# EE209_Schematic.net
KiCad netlist of a schematic drawn in Altium Designer
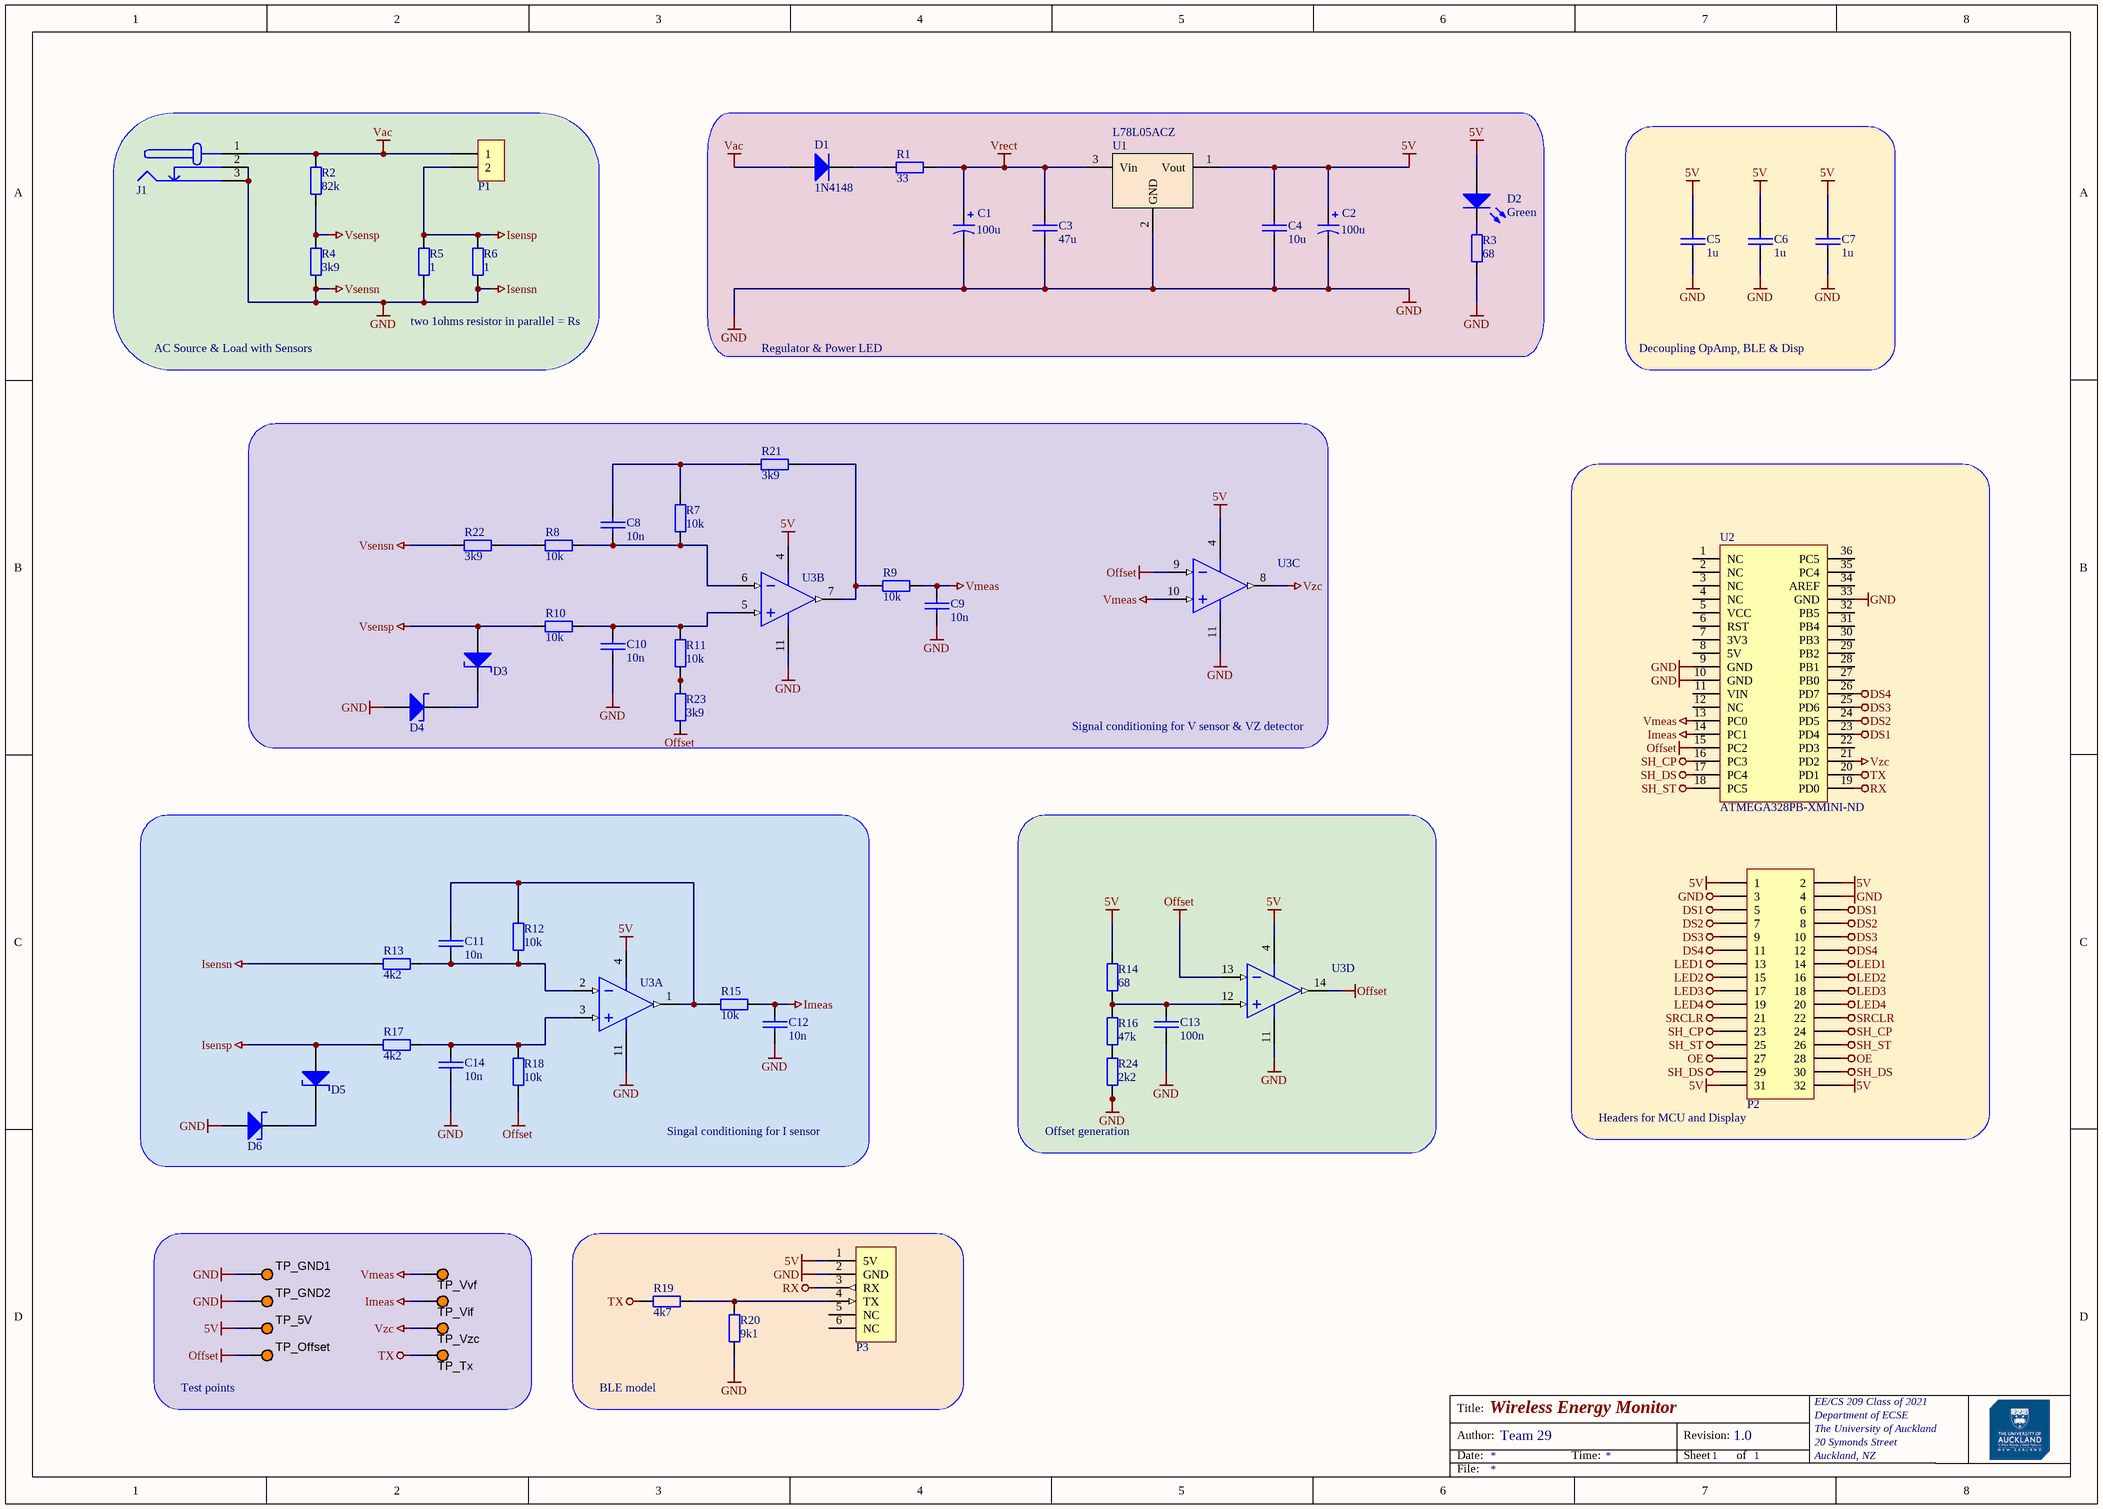
[diagram p0: EE209_Schematic.SchDoc]

(export (version "E")
  (design (tool "Eeschema 10.0.6"))
  (components
    (comp (ref "C1")
      (value "100u")
      (footprint "CAP-RAD-2.5mm Pitch")
      (description "Electrolytic capacitor with radial package, 2mm pitch and 5.2mm diameter")
      (fields (field (name "PUBLISHER") "Altium Limited"))
      (libsource (lib "EE209_Library") (part "ElecCap_TH_2P0"))
    )
    (comp (ref "C2")
      (value "100u")
      (footprint "CAP-RAD-2.5mm Pitch")
      (description "Electrolytic capacitor with radial package, 2mm pitch and 5.2mm diameter")
      (fields (field (name "PUBLISHER") "Altium Limited"))
      (libsource (lib "EE209_Library") (part "ElecCap_TH_2P0"))
    )
    (comp (ref "C3")
      (value "47u")
      (footprint "CCAP-5P0")
      (description "TH ceramic capacitor with 5mm pitch")
      (libsource (lib "EE209_Library") (part "CerCap_TH_5P0"))
    )
    (comp (ref "C4")
      (value "10u")
      (footprint "CCAP-5P0")
      (description "TH ceramic capacitor with 5mm pitch")
      (libsource (lib "EE209_Library") (part "CerCap_TH_5P0"))
    )
    (comp (ref "C5")
      (value "1u")
      (footprint "CCAP-5P0")
      (description "TH ceramic capacitor with 5mm pitch")
      (libsource (lib "EE209_Library") (part "CerCap_TH_5P0"))
    )
    (comp (ref "C6")
      (value "1u")
      (footprint "CCAP-5P0")
      (description "TH ceramic capacitor with 5mm pitch")
      (libsource (lib "EE209_Library") (part "CerCap_TH_5P0"))
    )
    (comp (ref "C7")
      (value "1u")
      (footprint "CCAP-5P0")
      (description "TH ceramic capacitor with 5mm pitch")
      (libsource (lib "EE209_Library") (part "CerCap_TH_5P0"))
    )
    (comp (ref "C8")
      (value "10n")
      (footprint "CCAP-5P0")
      (description "TH ceramic capacitor with 5mm pitch")
      (libsource (lib "EE209_Library") (part "CerCap_TH_5P0"))
    )
    (comp (ref "C9")
      (value "10n")
      (footprint "CCAP-5P0")
      (description "TH ceramic capacitor with 5mm pitch")
      (libsource (lib "EE209_Library") (part "CerCap_TH_5P0"))
    )
    (comp (ref "C10")
      (value "10n")
      (footprint "CCAP-5P0")
      (description "TH ceramic capacitor with 5mm pitch")
      (libsource (lib "EE209_Library") (part "CerCap_TH_5P0"))
    )
    (comp (ref "C11")
      (value "10n")
      (footprint "CCAP-5P0")
      (description "TH ceramic capacitor with 5mm pitch")
      (libsource (lib "EE209_Library") (part "CerCap_TH_5P0"))
    )
    (comp (ref "C12")
      (value "10n")
      (footprint "CCAP-5P0")
      (description "TH ceramic capacitor with 5mm pitch")
      (libsource (lib "EE209_Library") (part "CerCap_TH_5P0"))
    )
    (comp (ref "C13")
      (value "100n")
      (footprint "CCAP-5P0")
      (description "TH ceramic capacitor with 5mm pitch")
      (libsource (lib "EE209_Library") (part "CerCap_TH_5P0"))
    )
    (comp (ref "C14")
      (value "10n")
      (footprint "CCAP-5P0")
      (description "TH ceramic capacitor with 5mm pitch")
      (libsource (lib "EE209_Library") (part "CerCap_TH_5P0"))
    )
    (comp (ref "D1")
      (value "1N4148")
      (footprint "AXIAL-DIODE-0.4")
      (description "1N4148 100V 200mA axial diode")
      (fields
        (field (name "MANUFACTURER") "ON Semiconductor")
        (field (name "MANUFACTURER PART NUMBER") "1N4148TR")
      )
      (libsource (lib "EE209_Library") (part "1N4148_TH_4AX0"))
    )
    (comp (ref "D2")
      (value "Green")
      (footprint "LED")
      (description "Typical throughole GaAs LED with 2.54mm pitch")
      (fields (field (name "MANUFACTURER") "Generic Components") (field (name "PUBLISHER") "Altium Limited"))
      (libsource (lib "EE209_Library") (part "LED_TH_2P54"))
    )
    (comp (ref "D3")
      (value "BZX79-CXVX")
      (footprint "AXIAL-Zener-0.4")
      (description "Axial zener diode BZX79 series")
      (fields
        (field (name "MANUFACTURER") "Nexperia USA Inc.")
        (field (name "MANUFACTURER PART NUMBER") "BZX79-C4V7,143")
      )
      (libsource (lib "EE209_Library") (part "Zener_TH_4AX0"))
    )
    (comp (ref "D4")
      (value "BZX79-CXVX")
      (footprint "AXIAL-Zener-0.4")
      (description "Axial zener diode BZX79 series")
      (fields
        (field (name "MANUFACTURER") "Nexperia USA Inc.")
        (field (name "MANUFACTURER PART NUMBER") "BZX79-C4V7,143")
      )
      (libsource (lib "EE209_Library") (part "Zener_TH_4AX0"))
    )
    (comp (ref "D5")
      (value "BZX79-CXVX")
      (footprint "AXIAL-Zener-0.4")
      (description "Axial zener diode BZX79 series")
      (fields
        (field (name "MANUFACTURER") "Nexperia USA Inc.")
        (field (name "MANUFACTURER PART NUMBER") "BZX79-C4V7,143")
      )
      (libsource (lib "EE209_Library") (part "Zener_TH_4AX0"))
    )
    (comp (ref "D6")
      (value "BZX79-CXVX")
      (footprint "AXIAL-Zener-0.4")
      (description "Axial zener diode BZX79 series")
      (fields
        (field (name "MANUFACTURER") "Nexperia USA Inc.")
        (field (name "MANUFACTURER PART NUMBER") "BZX79-C4V7,143")
      )
      (libsource (lib "EE209_Library") (part "Zener_TH_4AX0"))
    )
    (comp (ref "J1")
      (value "DC barrel jack")
      (footprint "AC-Socket")
      (description "DC barrel jack connection to AC source")
      (libsource (lib "EE209_Library") (part "AC_Input"))
    )
    (comp (ref "P1")
      (value "Dual Banana Plugs")
      (footprint "Dual Banana Plug")
      (description "Dual banana plugs connection to the AC load")
      (fields (field (name "PUBLISHER") "Altium Limited"))
      (libsource (lib "EE209_Library") (part "AC_Output"))
    )
    (comp (ref "P2")
      (value "Display")
      (footprint "Display")
      (description "16-Pin Header Connecting Display")
      (libsource (lib "EE209_Library") (part "Display"))
    )
    (comp (ref "P3")
      (value "BLE Module Header")
      (footprint "HM10_HDR1X6")
      (description "2.54mm pitch 6-pin header for BLE module")
      (fields (field (name "PUBLISHER") "Altium Limited"))
      (libsource (lib "EE209_Library") (part "BLEModule_TH"))
    )
    (comp (ref "R1")
      (value "33")
      (footprint "AXIAL-0.4")
      (description "Through hole resistor")
      (fields (field (name "PUBLISHER") "Altium Limited"))
      (libsource (lib "") (part "Res_TH_0AX4_1"))
    )
    (comp (ref "R2")
      (value "82k")
      (footprint "AXIAL-0.4")
      (description "Through hole resistor")
      (fields (field (name "PUBLISHER") "Altium Limited"))
      (libsource (lib "EE209_Library") (part "Res_TH_0AX4"))
    )
    (comp (ref "R3")
      (value "68")
      (footprint "AXIAL-0.4")
      (description "Through hole resistor")
      (fields (field (name "PUBLISHER") "Altium Limited"))
      (libsource (lib "EE209_Library") (part "Res_TH_0AX4"))
    )
    (comp (ref "R4")
      (value "3k9")
      (footprint "AXIAL-0.4")
      (description "Through hole resistor")
      (fields (field (name "PUBLISHER") "Altium Limited"))
      (libsource (lib "EE209_Library") (part "Res_TH_0AX4"))
    )
    (comp (ref "R5")
      (value "1")
      (footprint "AXIAL-0.4")
      (description "Through hole resistor")
      (fields (field (name "PUBLISHER") "Altium Limited"))
      (libsource (lib "EE209_Library") (part "Res_TH_0AX4"))
    )
    (comp (ref "R6")
      (value "1")
      (footprint "AXIAL-0.4")
      (description "Through hole resistor")
      (fields (field (name "PUBLISHER") "Altium Limited"))
      (libsource (lib "EE209_Library") (part "Res_TH_0AX4"))
    )
    (comp (ref "R7")
      (value "10k")
      (footprint "AXIAL-0.4")
      (description "Through hole resistor")
      (fields (field (name "PUBLISHER") "Altium Limited"))
      (libsource (lib "EE209_Library") (part "Res_TH_0AX4"))
    )
    (comp (ref "R8")
      (value "10k")
      (footprint "AXIAL-0.4")
      (description "Through hole resistor")
      (fields (field (name "PUBLISHER") "Altium Limited"))
      (libsource (lib "") (part "Res_TH_0AX4_1"))
    )
    (comp (ref "R9")
      (value "10k")
      (footprint "AXIAL-0.4")
      (description "Through hole resistor")
      (fields (field (name "PUBLISHER") "Altium Limited"))
      (libsource (lib "") (part "Res_TH_0AX4_1"))
    )
    (comp (ref "R10")
      (value "10k")
      (footprint "AXIAL-0.4")
      (description "Through hole resistor")
      (fields (field (name "PUBLISHER") "Altium Limited"))
      (libsource (lib "") (part "Res_TH_0AX4_1"))
    )
    (comp (ref "R11")
      (value "10k")
      (footprint "AXIAL-0.4")
      (description "Through hole resistor")
      (fields (field (name "PUBLISHER") "Altium Limited"))
      (libsource (lib "EE209_Library") (part "Res_TH_0AX4"))
    )
    (comp (ref "R12")
      (value "10k")
      (footprint "AXIAL-0.4")
      (description "Through hole resistor")
      (fields (field (name "PUBLISHER") "Altium Limited"))
      (libsource (lib "EE209_Library") (part "Res_TH_0AX4"))
    )
    (comp (ref "R13")
      (value "4k2")
      (footprint "AXIAL-0.4")
      (description "Through hole resistor")
      (fields (field (name "PUBLISHER") "Altium Limited"))
      (libsource (lib "") (part "Res_TH_0AX4_1"))
    )
    (comp (ref "R14")
      (value "68")
      (footprint "AXIAL-0.4")
      (description "Through hole resistor")
      (fields (field (name "PUBLISHER") "Altium Limited"))
      (libsource (lib "EE209_Library") (part "Res_TH_0AX4"))
    )
    (comp (ref "R15")
      (value "10k")
      (footprint "AXIAL-0.4")
      (description "Through hole resistor")
      (fields (field (name "PUBLISHER") "Altium Limited"))
      (libsource (lib "") (part "Res_TH_0AX4_1"))
    )
    (comp (ref "R16")
      (value "47k")
      (footprint "AXIAL-0.4")
      (description "Through hole resistor")
      (fields (field (name "PUBLISHER") "Altium Limited"))
      (libsource (lib "EE209_Library") (part "Res_TH_0AX4"))
    )
    (comp (ref "R17")
      (value "4k2")
      (footprint "AXIAL-0.4")
      (description "Through hole resistor")
      (fields (field (name "PUBLISHER") "Altium Limited"))
      (libsource (lib "") (part "Res_TH_0AX4_1"))
    )
    (comp (ref "R18")
      (value "10k")
      (footprint "AXIAL-0.4")
      (description "Through hole resistor")
      (fields (field (name "PUBLISHER") "Altium Limited"))
      (libsource (lib "EE209_Library") (part "Res_TH_0AX4"))
    )
    (comp (ref "R19")
      (value "4k7")
      (footprint "AXIAL-0.4")
      (description "Through hole resistor")
      (fields (field (name "PUBLISHER") "Altium Limited"))
      (libsource (lib "") (part "Res_TH_0AX4_1"))
    )
    (comp (ref "R20")
      (value "9k1")
      (footprint "AXIAL-0.4")
      (description "Through hole resistor")
      (fields (field (name "PUBLISHER") "Altium Limited"))
      (libsource (lib "EE209_Library") (part "Res_TH_0AX4"))
    )
    (comp (ref "R21")
      (value "3k9")
      (footprint "AXIAL-0.4")
      (description "Through hole resistor")
      (fields (field (name "PUBLISHER") "Altium Limited"))
      (libsource (lib "") (part "Res_TH_0AX4_1"))
    )
    (comp (ref "R22")
      (value "3k9")
      (footprint "AXIAL-0.4")
      (description "Through hole resistor")
      (fields (field (name "PUBLISHER") "Altium Limited"))
      (libsource (lib "") (part "Res_TH_0AX4_1"))
    )
    (comp (ref "R23")
      (value "3k9")
      (footprint "AXIAL-0.4")
      (description "Through hole resistor")
      (fields (field (name "PUBLISHER") "Altium Limited"))
      (libsource (lib "EE209_Library") (part "Res_TH_0AX4"))
    )
    (comp (ref "R24")
      (value "2k2")
      (footprint "AXIAL-0.4")
      (description "Through hole resistor")
      (fields (field (name "PUBLISHER") "Altium Limited"))
      (libsource (lib "EE209_Library") (part "Res_TH_0AX4"))
    )
    (comp (ref "TP_5V")
      (value "5003")
      (footprint "TP_TH")
      (description "Test Point, Orange, 1-Pin THD, RoHS")
      (libsource (lib "EE209_Library") (part "TestPoint"))
    )
    (comp (ref "TP_GND1")
      (value "5003")
      (footprint "TP_TH")
      (description "Test Point, Orange, 1-Pin THD, RoHS")
      (libsource (lib "EE209_Library") (part "TestPoint"))
    )
    (comp (ref "TP_GND2")
      (value "5003")
      (footprint "TP_TH")
      (description "Test Point, Orange, 1-Pin THD, RoHS")
      (libsource (lib "EE209_Library") (part "TestPoint"))
    )
    (comp (ref "TP_Offset")
      (value "5003")
      (footprint "TP_TH")
      (description "Test Point, Orange, 1-Pin THD, RoHS")
      (libsource (lib "EE209_Library") (part "TestPoint"))
    )
    (comp (ref "TP_Tx")
      (value "5003")
      (footprint "TP_TH")
      (description "Test Point, Orange, 1-Pin THD, RoHS")
      (libsource (lib "EE209_Library") (part "TestPoint"))
    )
    (comp (ref "TP_Vif")
      (value "5003")
      (footprint "TP_TH")
      (description "Test Point, Orange, 1-Pin THD, RoHS")
      (libsource (lib "EE209_Library") (part "TestPoint"))
    )
    (comp (ref "TP_Vvf")
      (value "5003")
      (footprint "TP_TH")
      (description "Test Point, Orange, 1-Pin THD, RoHS")
      (libsource (lib "EE209_Library") (part "TestPoint"))
    )
    (comp (ref "TP_Vzc")
      (value "5003")
      (footprint "TP_TH")
      (description "Test Point, Orange, 1-Pin THD, RoHS")
      (libsource (lib "EE209_Library") (part "TestPoint"))
    )
    (comp (ref "U1")
      (value "L78L05ACZ")
      (footprint "TO-92")
      (description "Voltage Regulator 5V")
      (fields
        (field (name "MANUFACTURER") "ON Semiconductor")
        (field (name "MANUFACTURER PART NUMBER") "LM78L05ACZX")
      )
      (libsource (lib "EE209_Library") (part "L78L05_TH_TO92"))
    )
    (comp (ref "U2")
      (value "ATmega328PB Xplained Mini Header")
      (footprint "ATmeg328P Xplained")
      (description "Dual 18-pin headers connecting to ATmega328PB Xplained Mini")
      (fields
        (field (name "MANUFACTURER") "Microchip Technology")
        (field (name "MANUFACTURER PART NUMBER") "ATMEGA328PB-XMINI")
        (field (name "SUPPLIER PART NUMBER 1") "ATMEGA328PB-XMINI-ND")
      )
      (libsource (lib "EE209_Library") (part "ATmega328PBXplained_TH"))
    )
    (comp (ref "U3")
      (value "LM324")
      (footprint "DIP-14")
      (description "IC OPAMP GP 14DIP")
      (fields
        (field (name "MANUFACTURER") "ON Semiconductor")
        (field (name "MANUFACTURER PART NUMBER") "LM324N")
      )
      (libsource (lib "EE209_Library") (part "LM324N_TH_DIP16"))
    )
  )
  (nets
    (net (code "1") (name "5V") (class "Default")
      (node (ref "C2") (pin "1") (pinfunction "1_1") (pintype "passive"))
      (node (ref "C4") (pin "1") (pinfunction "1_1") (pintype "passive"))
      (node (ref "C5") (pin "1") (pinfunction "1_1") (pintype "passive"))
      (node (ref "C6") (pin "1") (pinfunction "1_1") (pintype "passive"))
      (node (ref "C7") (pin "1") (pinfunction "1_1") (pintype "passive"))
      (node (ref "D2") (pin "1") (pinfunction "A_1") (pintype "passive"))
      (node (ref "P2") (pin "1") (pinfunction "1_1") (pintype "passive"))
      (node (ref "P2") (pin "2") (pinfunction "2_2") (pintype "passive"))
      (node (ref "P2") (pin "31") (pinfunction "31_31") (pintype "passive"))
      (node (ref "P2") (pin "32") (pinfunction "32_32") (pintype "passive"))
      (node (ref "P3") (pin "1") (pinfunction "5V_1") (pintype "passive"))
      (node (ref "R14") (pin "2") (pinfunction "2_2") (pintype "passive"))
      (node (ref "TP_5V") (pin "1") (pinfunction "1_1") (pintype "passive"))
      (node (ref "U1") (pin "1") (pinfunction "Vout_1") (pintype "passive"))
      (node (ref "U3") (pin "4") (pinfunction "VDD_4") (pintype "power_in"))
    )
    (net (code "2") (name "DS1") (class "Default")
      (node (ref "P2") (pin "5") (pinfunction "5_5") (pintype "passive"))
      (node (ref "P2") (pin "6") (pinfunction "6_6") (pintype "passive"))
      (node (ref "U2") (pin "23") (pinfunction "PD4_23") (pintype "passive"))
    )
    (net (code "3") (name "DS2") (class "Default")
      (node (ref "P2") (pin "7") (pinfunction "7_7") (pintype "passive"))
      (node (ref "P2") (pin "8") (pinfunction "8_8") (pintype "passive"))
      (node (ref "U2") (pin "24") (pinfunction "PD5_24") (pintype "passive"))
    )
    (net (code "4") (name "DS3") (class "Default")
      (node (ref "P2") (pin "10") (pinfunction "10_10") (pintype "passive"))
      (node (ref "P2") (pin "9") (pinfunction "9_9") (pintype "passive"))
      (node (ref "U2") (pin "25") (pinfunction "PD6_25") (pintype "passive"))
    )
    (net (code "5") (name "DS4") (class "Default")
      (node (ref "P2") (pin "11") (pinfunction "11_11") (pintype "passive"))
      (node (ref "P2") (pin "12") (pinfunction "12_12") (pintype "passive"))
      (node (ref "U2") (pin "26") (pinfunction "PD7_26") (pintype "passive"))
    )
    (net (code "6") (name "GND") (class "Default")
      (node (ref "C1") (pin "2") (pinfunction "2_2") (pintype "passive"))
      (node (ref "C10") (pin "2") (pinfunction "2_2") (pintype "passive"))
      (node (ref "C12") (pin "2") (pinfunction "2_2") (pintype "passive"))
      (node (ref "C13") (pin "2") (pinfunction "2_2") (pintype "passive"))
      (node (ref "C14") (pin "2") (pinfunction "2_2") (pintype "passive"))
      (node (ref "C2") (pin "2") (pinfunction "2_2") (pintype "passive"))
      (node (ref "C3") (pin "2") (pinfunction "2_2") (pintype "passive"))
      (node (ref "C4") (pin "2") (pinfunction "2_2") (pintype "passive"))
      (node (ref "C5") (pin "2") (pinfunction "2_2") (pintype "passive"))
      (node (ref "C6") (pin "2") (pinfunction "2_2") (pintype "passive"))
      (node (ref "C7") (pin "2") (pinfunction "2_2") (pintype "passive"))
      (node (ref "C9") (pin "2") (pinfunction "2_2") (pintype "passive"))
      (node (ref "D4") (pin "1") (pinfunction "A_1") (pintype "passive"))
      (node (ref "D6") (pin "1") (pinfunction "A_1") (pintype "passive"))
      (node (ref "J1") (pin "2") (pinfunction "GND_ALT_2") (pintype "power_in"))
      (node (ref "J1") (pin "3") (pinfunction "GND_3") (pintype "power_in"))
      (node (ref "P2") (pin "3") (pinfunction "3_3") (pintype "passive"))
      (node (ref "P2") (pin "4") (pinfunction "4_4") (pintype "passive"))
      (node (ref "P3") (pin "2") (pinfunction "GND_2") (pintype "passive"))
      (node (ref "R13") (pin "1") (pinfunction "1_1") (pintype "passive"))
      (node (ref "R20") (pin "1") (pinfunction "1_1") (pintype "passive"))
      (node (ref "R22") (pin "1") (pinfunction "1_1") (pintype "passive"))
      (node (ref "R24") (pin "1") (pinfunction "1_1") (pintype "passive"))
      (node (ref "R3") (pin "1") (pinfunction "1_1") (pintype "passive"))
      (node (ref "R4") (pin "1") (pinfunction "1_1") (pintype "passive"))
      (node (ref "R5") (pin "1") (pinfunction "1_1") (pintype "passive"))
      (node (ref "R6") (pin "1") (pinfunction "1_1") (pintype "passive"))
      (node (ref "TP_GND1") (pin "1") (pinfunction "1_1") (pintype "passive"))
      (node (ref "TP_GND2") (pin "1") (pinfunction "1_1") (pintype "passive"))
      (node (ref "U1") (pin "2") (pinfunction "GND_2") (pintype "passive"))
      (node (ref "U2") (pin "10") (pinfunction "GND_10") (pintype "power_in"))
      (node (ref "U2") (pin "33") (pinfunction "GND_33") (pintype "passive"))
      (node (ref "U2") (pin "9") (pinfunction "GND_9") (pintype "power_in"))
      (node (ref "U3") (pin "11") (pinfunction "VSS_11") (pintype "power_in"))
    )
    (net (code "7") (name "Imeas") (class "Default")
      (node (ref "C12") (pin "1") (pinfunction "1_1") (pintype "passive"))
      (node (ref "R15") (pin "2") (pinfunction "2_2") (pintype "passive"))
      (node (ref "TP_Vif") (pin "1") (pinfunction "1_1") (pintype "passive"))
      (node (ref "U2") (pin "14") (pinfunction "PC1_14") (pintype "passive"))
    )
    (net (code "8") (name "Isensp") (class "Default")
      (node (ref "D5") (pin "1") (pinfunction "A_1") (pintype "passive"))
      (node (ref "P1") (pin "2") (pinfunction "2_2") (pintype "passive"))
      (node (ref "R17") (pin "1") (pinfunction "1_1") (pintype "passive"))
      (node (ref "R5") (pin "2") (pinfunction "2_2") (pintype "passive"))
      (node (ref "R6") (pin "2") (pinfunction "2_2") (pintype "passive"))
    )
    (net (code "9") (name "LED1") (class "Default")
      (node (ref "P2") (pin "13") (pinfunction "13_13") (pintype "passive"))
      (node (ref "P2") (pin "14") (pinfunction "14_14") (pintype "passive"))
    )
    (net (code "10") (name "LED2") (class "Default")
      (node (ref "P2") (pin "15") (pinfunction "15_15") (pintype "passive"))
      (node (ref "P2") (pin "16") (pinfunction "16_16") (pintype "passive"))
    )
    (net (code "11") (name "LED3") (class "Default")
      (node (ref "P2") (pin "17") (pinfunction "17_17") (pintype "passive"))
      (node (ref "P2") (pin "18") (pinfunction "18_18") (pintype "passive"))
    )
    (net (code "12") (name "LED4") (class "Default")
      (node (ref "P2") (pin "19") (pinfunction "19_19") (pintype "passive"))
      (node (ref "P2") (pin "20") (pinfunction "20_20") (pintype "passive"))
    )
    (net (code "13") (name "Net-(C8-Pad1)") (class "Default")
      (node (ref "C8") (pin "1") (pinfunction "1_1") (pintype "passive"))
      (node (ref "R21") (pin "1") (pinfunction "1_1") (pintype "passive"))
      (node (ref "R7") (pin "2") (pinfunction "2_2") (pintype "passive"))
    )
    (net (code "14") (name "Net-(D1-K)") (class "Default")
      (node (ref "D1") (pin "2") (pinfunction "K_2") (pintype "passive"))
      (node (ref "R1") (pin "1") (pinfunction "1_1") (pintype "passive"))
    )
    (net (code "15") (name "Net-(D2-K)") (class "Default")
      (node (ref "D2") (pin "2") (pinfunction "K_2") (pintype "passive"))
      (node (ref "R3") (pin "2") (pinfunction "2_2") (pintype "passive"))
    )
    (net (code "16") (name "Net-(D3-K)") (class "Default")
      (node (ref "D3") (pin "2") (pinfunction "K_2") (pintype "passive"))
      (node (ref "D4") (pin "2") (pinfunction "K_2") (pintype "passive"))
    )
    (net (code "17") (name "Net-(D5-K)") (class "Default")
      (node (ref "D5") (pin "2") (pinfunction "K_2") (pintype "passive"))
      (node (ref "D6") (pin "2") (pinfunction "K_2") (pintype "passive"))
    )
    (net (code "18") (name "Net-(P3-TX)") (class "Default")
      (node (ref "P3") (pin "4") (pinfunction "TX_4") (pintype "input"))
      (node (ref "R19") (pin "2") (pinfunction "2_2") (pintype "passive"))
      (node (ref "R20") (pin "2") (pinfunction "2_2") (pintype "passive"))
    )
    (net (code "19") (name "Net-(R11-Pad1)") (class "Default")
      (node (ref "R11") (pin "1") (pinfunction "1_1") (pintype "passive"))
      (node (ref "R23") (pin "2") (pinfunction "2_2") (pintype "passive"))
    )
    (net (code "20") (name "Net-(R22-Pad2)") (class "Default")
      (node (ref "R22") (pin "2") (pinfunction "2_2") (pintype "passive"))
      (node (ref "R8") (pin "1") (pinfunction "1_1") (pintype "passive"))
    )
    (net (code "21") (name "Net-(U3A-VINA+)") (class "Default")
      (node (ref "C14") (pin "1") (pinfunction "1_1") (pintype "passive"))
      (node (ref "R17") (pin "2") (pinfunction "2_2") (pintype "passive"))
      (node (ref "R18") (pin "2") (pinfunction "2_2") (pintype "passive"))
      (node (ref "U3") (pin "3") (pinfunction "VINA+_3") (pintype "input"))
    )
    (net (code "22") (name "Net-(U3A-VINA-)") (class "Default")
      (node (ref "C11") (pin "2") (pinfunction "2_2") (pintype "passive"))
      (node (ref "R12") (pin "1") (pinfunction "1_1") (pintype "passive"))
      (node (ref "R13") (pin "2") (pinfunction "2_2") (pintype "passive"))
      (node (ref "U3") (pin "2") (pinfunction "VINA-_2") (pintype "input"))
    )
    (net (code "23") (name "Net-(U3A-VOUTA)") (class "Default")
      (node (ref "C11") (pin "1") (pinfunction "1_1") (pintype "passive"))
      (node (ref "R12") (pin "2") (pinfunction "2_2") (pintype "passive"))
      (node (ref "R15") (pin "1") (pinfunction "1_1") (pintype "passive"))
      (node (ref "U3") (pin "1") (pinfunction "VOUTA_1") (pintype "output"))
    )
    (net (code "24") (name "Net-(U3B-VINB+)") (class "Default")
      (node (ref "C10") (pin "1") (pinfunction "1_1") (pintype "passive"))
      (node (ref "R10") (pin "2") (pinfunction "2_2") (pintype "passive"))
      (node (ref "R11") (pin "2") (pinfunction "2_2") (pintype "passive"))
      (node (ref "U3") (pin "5") (pinfunction "VINB+_5") (pintype "input"))
    )
    (net (code "25") (name "Net-(U3B-VINB-)") (class "Default")
      (node (ref "C8") (pin "2") (pinfunction "2_2") (pintype "passive"))
      (node (ref "R7") (pin "1") (pinfunction "1_1") (pintype "passive"))
      (node (ref "R8") (pin "2") (pinfunction "2_2") (pintype "passive"))
      (node (ref "U3") (pin "6") (pinfunction "VINB-_6") (pintype "input"))
    )
    (net (code "26") (name "Net-(U3B-VOUTB)") (class "Default")
      (node (ref "R21") (pin "2") (pinfunction "2_2") (pintype "passive"))
      (node (ref "R9") (pin "1") (pinfunction "1_1") (pintype "passive"))
      (node (ref "U3") (pin "7") (pinfunction "VOUTB_7") (pintype "output"))
    )
    (net (code "27") (name "Net-(U3D-VIND+)") (class "Default")
      (node (ref "C13") (pin "1") (pinfunction "1_1") (pintype "passive"))
      (node (ref "R14") (pin "1") (pinfunction "1_1") (pintype "passive"))
      (node (ref "R16") (pin "2") (pinfunction "2_2") (pintype "passive"))
      (node (ref "U3") (pin "12") (pinfunction "VIND+_12") (pintype "input"))
    )
    (net (code "28") (name "OE") (class "Default")
      (node (ref "P2") (pin "27") (pinfunction "27_27") (pintype "passive"))
      (node (ref "P2") (pin "28") (pinfunction "28_28") (pintype "passive"))
    )
    (net (code "29") (name "Offset") (class "Default")
      (node (ref "R18") (pin "1") (pinfunction "1_1") (pintype "passive"))
      (node (ref "TP_Offset") (pin "1") (pinfunction "1_1") (pintype "passive"))
      (node (ref "U2") (pin "15") (pinfunction "PC2_15") (pintype "passive"))
      (node (ref "U3") (pin "13") (pinfunction "VIND-_13") (pintype "input"))
      (node (ref "U3") (pin "14") (pinfunction "VOUTD_14") (pintype "output"))
      (node (ref "U3") (pin "9") (pinfunction "VINC-_9") (pintype "input"))
    )
    (net (code "30") (name "RX") (class "Default")
      (node (ref "P3") (pin "3") (pinfunction "RX_3") (pintype "output"))
      (node (ref "U2") (pin "19") (pinfunction "PD0_19") (pintype "passive"))
    )
    (net (code "31") (name "SH_CP") (class "Default")
      (node (ref "P2") (pin "23") (pinfunction "23_23") (pintype "passive"))
      (node (ref "P2") (pin "24") (pinfunction "24_24") (pintype "passive"))
      (node (ref "U2") (pin "16") (pinfunction "PC3_16") (pintype "passive"))
    )
    (net (code "32") (name "SH_DS") (class "Default")
      (node (ref "P2") (pin "29") (pinfunction "29_29") (pintype "passive"))
      (node (ref "P2") (pin "30") (pinfunction "30_30") (pintype "passive"))
      (node (ref "U2") (pin "17") (pinfunction "PC4_17") (pintype "passive"))
    )
    (net (code "33") (name "SH_ST") (class "Default")
      (node (ref "P2") (pin "25") (pinfunction "25_25") (pintype "passive"))
      (node (ref "P2") (pin "26") (pinfunction "26_26") (pintype "passive"))
      (node (ref "U2") (pin "18") (pinfunction "PC5_18") (pintype "passive"))
    )
    (net (code "34") (name "SRCLR") (class "Default")
      (node (ref "P2") (pin "21") (pinfunction "21_21") (pintype "passive"))
      (node (ref "P2") (pin "22") (pinfunction "22_22") (pintype "passive"))
    )
    (net (code "35") (name "TX") (class "Default")
      (node (ref "R19") (pin "1") (pinfunction "1_1") (pintype "passive"))
      (node (ref "TP_Tx") (pin "1") (pinfunction "1_1") (pintype "passive"))
      (node (ref "U2") (pin "20") (pinfunction "PD1_20") (pintype "passive"))
    )
    (net (code "36") (name "Vac") (class "Default")
      (node (ref "D1") (pin "1") (pinfunction "A_1") (pintype "passive"))
      (node (ref "J1") (pin "1") (pinfunction "VCC_1") (pintype "power_in"))
      (node (ref "P1") (pin "1") (pinfunction "1_1") (pintype "passive"))
      (node (ref "R2") (pin "2") (pinfunction "2_2") (pintype "passive"))
    )
    (net (code "37") (name "Vmeas") (class "Default")
      (node (ref "C9") (pin "1") (pinfunction "1_1") (pintype "passive"))
      (node (ref "R9") (pin "2") (pinfunction "2_2") (pintype "passive"))
      (node (ref "TP_Vvf") (pin "1") (pinfunction "1_1") (pintype "passive"))
      (node (ref "U2") (pin "13") (pinfunction "PC0_13") (pintype "passive"))
      (node (ref "U3") (pin "10") (pinfunction "VINC+_10") (pintype "input"))
    )
    (net (code "38") (name "Vrect") (class "Default")
      (node (ref "C1") (pin "1") (pinfunction "1_1") (pintype "passive"))
      (node (ref "C3") (pin "1") (pinfunction "1_1") (pintype "passive"))
      (node (ref "R1") (pin "2") (pinfunction "2_2") (pintype "passive"))
      (node (ref "U1") (pin "3") (pinfunction "Vin_3") (pintype "passive"))
    )
    (net (code "39") (name "Vsensp") (class "Default")
      (node (ref "D3") (pin "1") (pinfunction "A_1") (pintype "passive"))
      (node (ref "R10") (pin "1") (pinfunction "1_1") (pintype "passive"))
      (node (ref "R2") (pin "1") (pinfunction "1_1") (pintype "passive"))
      (node (ref "R4") (pin "2") (pinfunction "2_2") (pintype "passive"))
    )
    (net (code "40") (name "Vzc") (class "Default")
      (node (ref "TP_Vzc") (pin "1") (pinfunction "1_1") (pintype "passive"))
      (node (ref "U2") (pin "21") (pinfunction "PD2_21") (pintype "passive"))
      (node (ref "U3") (pin "8") (pinfunction "VOUTC_8") (pintype "output"))
    )
    (net (code "41") (name "unconnected-(P3-NC-Pad5)") (class "Default")
      (node (ref "P3") (pin "5") (pinfunction "NC_5") (pintype "passive"))
    )
    (net (code "42") (name "unconnected-(P3-NC-Pad6)") (class "Default")
      (node (ref "P3") (pin "6") (pinfunction "NC_6") (pintype "passive"))
    )
    (net (code "43") (name "unconnected-(R16-Pad1)") (class "Default")
      (node (ref "R16") (pin "1") (pinfunction "1_1") (pintype "passive"))
    )
    (net (code "44") (name "unconnected-(R23-Pad1)") (class "Default")
      (node (ref "R23") (pin "1") (pinfunction "1_1") (pintype "passive"))
    )
    (net (code "45") (name "unconnected-(R24-Pad2)") (class "Default")
      (node (ref "R24") (pin "2") (pinfunction "2_2") (pintype "passive"))
    )
    (net (code "46") (name "unconnected-(U2-3V3-Pad7)") (class "Default")
      (node (ref "U2") (pin "7") (pinfunction "3V3_7") (pintype "passive"))
    )
    (net (code "47") (name "unconnected-(U2-5V-Pad8)") (class "Default")
      (node (ref "U2") (pin "8") (pinfunction "5V_8") (pintype "power_in"))
    )
    (net (code "48") (name "unconnected-(U2-AREF-Pad34)") (class "Default")
      (node (ref "U2") (pin "34") (pinfunction "AREF_34") (pintype "passive"))
    )
    (net (code "49") (name "unconnected-(U2-NC-Pad1)") (class "Default")
      (node (ref "U2") (pin "1") (pinfunction "NC_1") (pintype "passive"))
    )
    (net (code "50") (name "unconnected-(U2-NC-Pad2)") (class "Default")
      (node (ref "U2") (pin "2") (pinfunction "NC_2") (pintype "passive"))
    )
    (net (code "51") (name "unconnected-(U2-NC-Pad3)") (class "Default")
      (node (ref "U2") (pin "3") (pinfunction "NC_3") (pintype "passive"))
    )
    (net (code "52") (name "unconnected-(U2-NC-Pad4)") (class "Default")
      (node (ref "U2") (pin "4") (pinfunction "NC_4") (pintype "passive"))
    )
    (net (code "53") (name "unconnected-(U2-NC-Pad12)") (class "Default")
      (node (ref "U2") (pin "12") (pinfunction "NC_12") (pintype "passive"))
    )
    (net (code "54") (name "unconnected-(U2-PB0-Pad27)") (class "Default")
      (node (ref "U2") (pin "27") (pinfunction "PB0_27") (pintype "passive"))
    )
    (net (code "55") (name "unconnected-(U2-PB1-Pad28)") (class "Default")
      (node (ref "U2") (pin "28") (pinfunction "PB1_28") (pintype "passive"))
    )
    (net (code "56") (name "unconnected-(U2-PB2-Pad29)") (class "Default")
      (node (ref "U2") (pin "29") (pinfunction "PB2_29") (pintype "passive"))
    )
    (net (code "57") (name "unconnected-(U2-PB3-Pad30)") (class "Default")
      (node (ref "U2") (pin "30") (pinfunction "PB3_30") (pintype "passive"))
    )
    (net (code "58") (name "unconnected-(U2-PB4-Pad31)") (class "Default")
      (node (ref "U2") (pin "31") (pinfunction "PB4_31") (pintype "passive"))
    )
    (net (code "59") (name "unconnected-(U2-PB5-Pad32)") (class "Default")
      (node (ref "U2") (pin "32") (pinfunction "PB5_32") (pintype "passive"))
    )
    (net (code "60") (name "unconnected-(U2-PC4-Pad35)") (class "Default")
      (node (ref "U2") (pin "35") (pinfunction "PC4_35") (pintype "passive"))
    )
    (net (code "61") (name "unconnected-(U2-PC5-Pad36)") (class "Default")
      (node (ref "U2") (pin "36") (pinfunction "PC5_36") (pintype "passive"))
    )
    (net (code "62") (name "unconnected-(U2-PD3-Pad22)") (class "Default")
      (node (ref "U2") (pin "22") (pinfunction "PD3_22") (pintype "passive"))
    )
    (net (code "63") (name "unconnected-(U2-RST-Pad6)") (class "Default")
      (node (ref "U2") (pin "6") (pinfunction "RST_6") (pintype "passive"))
    )
    (net (code "64") (name "unconnected-(U2-VCC-Pad5)") (class "Default")
      (node (ref "U2") (pin "5") (pinfunction "VCC_5") (pintype "power_in"))
    )
    (net (code "65") (name "unconnected-(U2-VIN-Pad11)") (class "Default")
      (node (ref "U2") (pin "11") (pinfunction "VIN_11") (pintype "power_in"))
    )
  )
)
